# 1_P1.net
KiCad netlist of a schematic drawn in Altium Designer
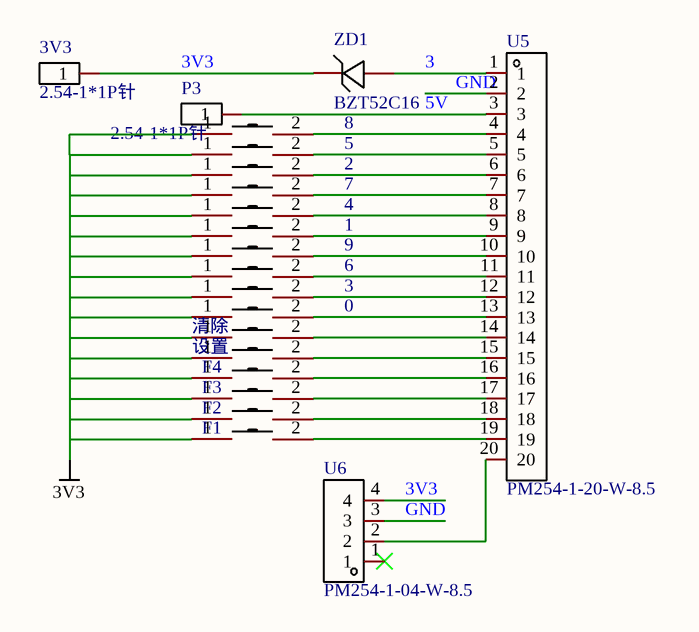
[diagram p0: 1_P1.schdoc]

(export (version "E")
  (design (tool "Eeschema 10.0.6"))
  (components
    (comp (ref "0")
      (value "TS-1101-C-W")
      (fields (field (name "MANUFACTURER") "XKB Connectivity(中国星坤)"))
      (libsource (lib "altium-import") (part "root_0_TS-1101-C-W_"))
    )
    (comp (ref "1")
      (value "TS-1101-C-W")
      (fields (field (name "MANUFACTURER") "XKB Connectivity(中国星坤)"))
      (libsource (lib "altium-import") (part "root_0_TS-1101-C-W_"))
    )
    (comp (ref "2")
      (value "TS-1101-C-W")
      (fields (field (name "MANUFACTURER") "XKB Connectivity(中国星坤)"))
      (libsource (lib "altium-import") (part "root_0_TS-1101-C-W_"))
    )
    (comp (ref "3")
      (value "TS-1101-C-W")
      (fields (field (name "MANUFACTURER") "XKB Connectivity(中国星坤)"))
      (libsource (lib "altium-import") (part "root_0_TS-1101-C-W_"))
    )
    (comp (ref "3V3")
      (value "2.54-1*1P针")
      (description "排数:单排;总PIN位数:1;间距:-;插针结构:-;行距:-;安装类型:直插;圆针/方针:-;额定电流:-;额定电压:-;配合针长度:-;塑高:-;触头材质:-;触头镀层:-;颜色:黑色;")
      (fields (field (name "NAME") "2.54-1*1P针") (field (name "MANUFACTURER") "BOOMELE(博穆精密)"))
      (libsource (lib "altium-import") (part "root_2_2.54-1*1P针_"))
    )
    (comp (ref "4")
      (value "TS-1101-C-W")
      (fields (field (name "MANUFACTURER") "XKB Connectivity(中国星坤)"))
      (libsource (lib "altium-import") (part "root_0_TS-1101-C-W_"))
    )
    (comp (ref "5")
      (value "TS-1101-C-W")
      (fields (field (name "MANUFACTURER") "XKB Connectivity(中国星坤)"))
      (libsource (lib "altium-import") (part "root_0_TS-1101-C-W_"))
    )
    (comp (ref "6")
      (value "TS-1101-C-W")
      (fields (field (name "MANUFACTURER") "XKB Connectivity(中国星坤)"))
      (libsource (lib "altium-import") (part "root_0_TS-1101-C-W_"))
    )
    (comp (ref "7")
      (value "TS-1101-C-W")
      (fields (field (name "MANUFACTURER") "XKB Connectivity(中国星坤)"))
      (libsource (lib "altium-import") (part "root_0_TS-1101-C-W_"))
    )
    (comp (ref "8")
      (value "TS-1101-C-W")
      (fields (field (name "MANUFACTURER") "XKB Connectivity(中国星坤)"))
      (libsource (lib "altium-import") (part "root_0_TS-1101-C-W_"))
    )
    (comp (ref "9")
      (value "TS-1101-C-W")
      (fields (field (name "MANUFACTURER") "XKB Connectivity(中国星坤)"))
      (libsource (lib "altium-import") (part "root_0_TS-1101-C-W_"))
    )
    (comp (ref "F1")
      (value "TS-1101-C-W")
      (fields (field (name "MANUFACTURER") "XKB Connectivity(中国星坤)"))
      (libsource (lib "altium-import") (part "root_0_TS-1101-C-W_"))
    )
    (comp (ref "F2")
      (value "TS-1101-C-W")
      (fields (field (name "MANUFACTURER") "XKB Connectivity(中国星坤)"))
      (libsource (lib "altium-import") (part "root_0_TS-1101-C-W_"))
    )
    (comp (ref "F3")
      (value "TS-1101-C-W")
      (fields (field (name "MANUFACTURER") "XKB Connectivity(中国星坤)"))
      (libsource (lib "altium-import") (part "root_0_TS-1101-C-W_"))
    )
    (comp (ref "F4")
      (value "TS-1101-C-W")
      (fields (field (name "MANUFACTURER") "XKB Connectivity(中国星坤)"))
      (libsource (lib "altium-import") (part "root_0_TS-1101-C-W_"))
    )
    (comp (ref "P3")
      (value "2.54-1*1P针")
      (description "排数:单排;总PIN位数:1;间距:-;插针结构:-;行距:-;安装类型:直插;圆针/方针:-;额定电流:-;额定电压:-;配合针长度:-;塑高:-;触头材质:-;触头镀层:-;颜色:黑色;")
      (fields (field (name "NAME") "2.54-1*1P针") (field (name "MANUFACTURER") "BOOMELE(博穆精密)"))
      (libsource (lib "altium-import") (part "root_2_2.54-1*1P针_"))
    )
    (comp (ref "U5")
      (value "PM254-1-20-W-8.5")
      (fields (field (name "NAME") "PM254-1-20-W-8.5") (field (name "MANUFACTURER") "HCTL(华灿天禄)"))
      (libsource (lib "altium-import") (part "root_0_PM254-1-20-W-8.5_"))
    )
    (comp (ref "U6")
      (value "PM254-1-04-W-8.5")
      (description "2.54MM单排排母塑高8.5 1*4 弯插")
      (fields (field (name "NAME") "PM254-1-04-W-8.5") (field (name "MANUFACTURER") "HCTL(华灿天禄)"))
      (libsource (lib "altium-import") (part "root_2_PM254-1-04-W-8.5_"))
    )
    (comp (ref "ZD1")
      (value "BZT52C16")
      (description "二极管配置:独立式;稳压值(标称值):16V;稳压值(范围):15.3V~17.1V;精度:-;功率:350mW;反向电流(Ir):100nA@11.2V;阻抗(Zzt):40Ω;")
      (fields (field (name "NAME") "BZT52C16") (field (name "MANUFACTURER") "CJ（江苏长电/长晶）"))
      (libsource (lib "altium-import") (part "root_0_BZT52C16_C2105_"))
    )
    (comp (ref "清除")
      (value "TS-1101-C-W")
      (fields (field (name "MANUFACTURER") "XKB Connectivity(中国星坤)"))
      (libsource (lib "altium-import") (part "root_0_TS-1101-C-W_"))
    )
    (comp (ref "设置")
      (value "TS-1101-C-W")
      (fields (field (name "MANUFACTURER") "XKB Connectivity(中国星坤)"))
      (libsource (lib "altium-import") (part "root_0_TS-1101-C-W_"))
    )
  )
  (nets
    (net (code "1") (name "/3") (class "Default")
      (node (ref "U5") (pin "1") (pinfunction "1_1") (pintype "passive"))
      (node (ref "ZD1") (pin "2") (pinfunction "A_2") (pintype "passive"))
    )
    (net (code "2") (name "/5V") (class "Default")
      (node (ref "P3") (pin "1") (pinfunction "1_1") (pintype "passive"))
      (node (ref "U5") (pin "3") (pinfunction "3_3") (pintype "passive"))
    )
    (net (code "3") (name "/GND") (class "Default")
      (node (ref "U5") (pin "2") (pinfunction "2_2") (pintype "passive"))
      (node (ref "U6") (pin "3") (pinfunction "3_3") (pintype "passive"))
    )
    (net (code "4") (name "3V3") (class "Default")
      (node (ref "0") (pin "1") (pinfunction "1_1") (pintype "passive"))
      (node (ref "1") (pin "1") (pinfunction "1_1") (pintype "passive"))
      (node (ref "2") (pin "1") (pinfunction "1_1") (pintype "passive"))
      (node (ref "3") (pin "1") (pinfunction "1_1") (pintype "passive"))
      (node (ref "3V3") (pin "1") (pinfunction "1_1") (pintype "passive"))
      (node (ref "4") (pin "1") (pinfunction "1_1") (pintype "passive"))
      (node (ref "5") (pin "1") (pinfunction "1_1") (pintype "passive"))
      (node (ref "6") (pin "1") (pinfunction "1_1") (pintype "passive"))
      (node (ref "7") (pin "1") (pinfunction "1_1") (pintype "passive"))
      (node (ref "8") (pin "1") (pinfunction "1_1") (pintype "passive"))
      (node (ref "9") (pin "1") (pinfunction "1_1") (pintype "passive"))
      (node (ref "F1") (pin "1") (pinfunction "1_1") (pintype "passive"))
      (node (ref "F2") (pin "1") (pinfunction "1_1") (pintype "passive"))
      (node (ref "F3") (pin "1") (pinfunction "1_1") (pintype "passive"))
      (node (ref "F4") (pin "1") (pinfunction "1_1") (pintype "passive"))
      (node (ref "U6") (pin "4") (pinfunction "4_4") (pintype "passive"))
      (node (ref "ZD1") (pin "1") (pinfunction "K_1") (pintype "passive"))
      (node (ref "清除") (pin "1") (pinfunction "1_1") (pintype "passive"))
      (node (ref "设置") (pin "1") (pinfunction "1_1") (pintype "passive"))
    )
    (net (code "5") (name "Net-(0-Pad2)") (class "Default")
      (node (ref "0") (pin "2") (pinfunction "2_2") (pintype "passive"))
      (node (ref "U5") (pin "13") (pinfunction "13_13") (pintype "passive"))
    )
    (net (code "6") (name "Net-(1-Pad2)") (class "Default")
      (node (ref "1") (pin "2") (pinfunction "2_2") (pintype "passive"))
      (node (ref "U5") (pin "9") (pinfunction "9_9") (pintype "passive"))
    )
    (net (code "7") (name "Net-(2-Pad2)") (class "Default")
      (node (ref "2") (pin "2") (pinfunction "2_2") (pintype "passive"))
      (node (ref "U5") (pin "6") (pinfunction "6_6") (pintype "passive"))
    )
    (net (code "8") (name "Net-(3-Pad2)") (class "Default")
      (node (ref "3") (pin "2") (pinfunction "2_2") (pintype "passive"))
      (node (ref "U5") (pin "12") (pinfunction "12_12") (pintype "passive"))
    )
    (net (code "9") (name "Net-(4-Pad2)") (class "Default")
      (node (ref "4") (pin "2") (pinfunction "2_2") (pintype "passive"))
      (node (ref "U5") (pin "8") (pinfunction "8_8") (pintype "passive"))
    )
    (net (code "10") (name "Net-(5-Pad2)") (class "Default")
      (node (ref "5") (pin "2") (pinfunction "2_2") (pintype "passive"))
      (node (ref "U5") (pin "5") (pinfunction "5_5") (pintype "passive"))
    )
    (net (code "11") (name "Net-(6-Pad2)") (class "Default")
      (node (ref "6") (pin "2") (pinfunction "2_2") (pintype "passive"))
      (node (ref "U5") (pin "11") (pinfunction "11_11") (pintype "passive"))
    )
    (net (code "12") (name "Net-(7-Pad2)") (class "Default")
      (node (ref "7") (pin "2") (pinfunction "2_2") (pintype "passive"))
      (node (ref "U5") (pin "7") (pinfunction "7_7") (pintype "passive"))
    )
    (net (code "13") (name "Net-(8-Pad2)") (class "Default")
      (node (ref "8") (pin "2") (pinfunction "2_2") (pintype "passive"))
      (node (ref "U5") (pin "4") (pinfunction "4_4") (pintype "passive"))
    )
    (net (code "14") (name "Net-(9-Pad2)") (class "Default")
      (node (ref "9") (pin "2") (pinfunction "2_2") (pintype "passive"))
      (node (ref "U5") (pin "10") (pinfunction "10_10") (pintype "passive"))
    )
    (net (code "15") (name "Net-(F1-Pad2)") (class "Default")
      (node (ref "F1") (pin "2") (pinfunction "2_2") (pintype "passive"))
      (node (ref "U5") (pin "19") (pinfunction "19_19") (pintype "passive"))
    )
    (net (code "16") (name "Net-(F2-Pad2)") (class "Default")
      (node (ref "F2") (pin "2") (pinfunction "2_2") (pintype "passive"))
      (node (ref "U5") (pin "18") (pinfunction "18_18") (pintype "passive"))
    )
    (net (code "17") (name "Net-(F3-Pad2)") (class "Default")
      (node (ref "F3") (pin "2") (pinfunction "2_2") (pintype "passive"))
      (node (ref "U5") (pin "17") (pinfunction "17_17") (pintype "passive"))
    )
    (net (code "18") (name "Net-(F4-Pad2)") (class "Default")
      (node (ref "F4") (pin "2") (pinfunction "2_2") (pintype "passive"))
      (node (ref "U5") (pin "16") (pinfunction "16_16") (pintype "passive"))
    )
    (net (code "19") (name "Net-(U5-Pad14)") (class "Default")
      (node (ref "U5") (pin "14") (pinfunction "14_14") (pintype "passive"))
      (node (ref "清除") (pin "2") (pinfunction "2_2") (pintype "passive"))
    )
    (net (code "20") (name "Net-(U5-Pad15)") (class "Default")
      (node (ref "U5") (pin "15") (pinfunction "15_15") (pintype "passive"))
      (node (ref "设置") (pin "2") (pinfunction "2_2") (pintype "passive"))
    )
    (net (code "21") (name "Net-(U5-Pad20)") (class "Default")
      (node (ref "U5") (pin "20") (pinfunction "20_20") (pintype "passive"))
      (node (ref "U6") (pin "2") (pinfunction "2_2") (pintype "passive"))
    )
    (net (code "22") (name "unconnected-(U6-Pad1)") (class "Default")
      (node (ref "U6") (pin "1") (pinfunction "1_1") (pintype "passive+no_connect"))
    )
  )
)
